# UNO_lowcost_V11.net
KiCad netlist of a schematic drawn in EAGLE
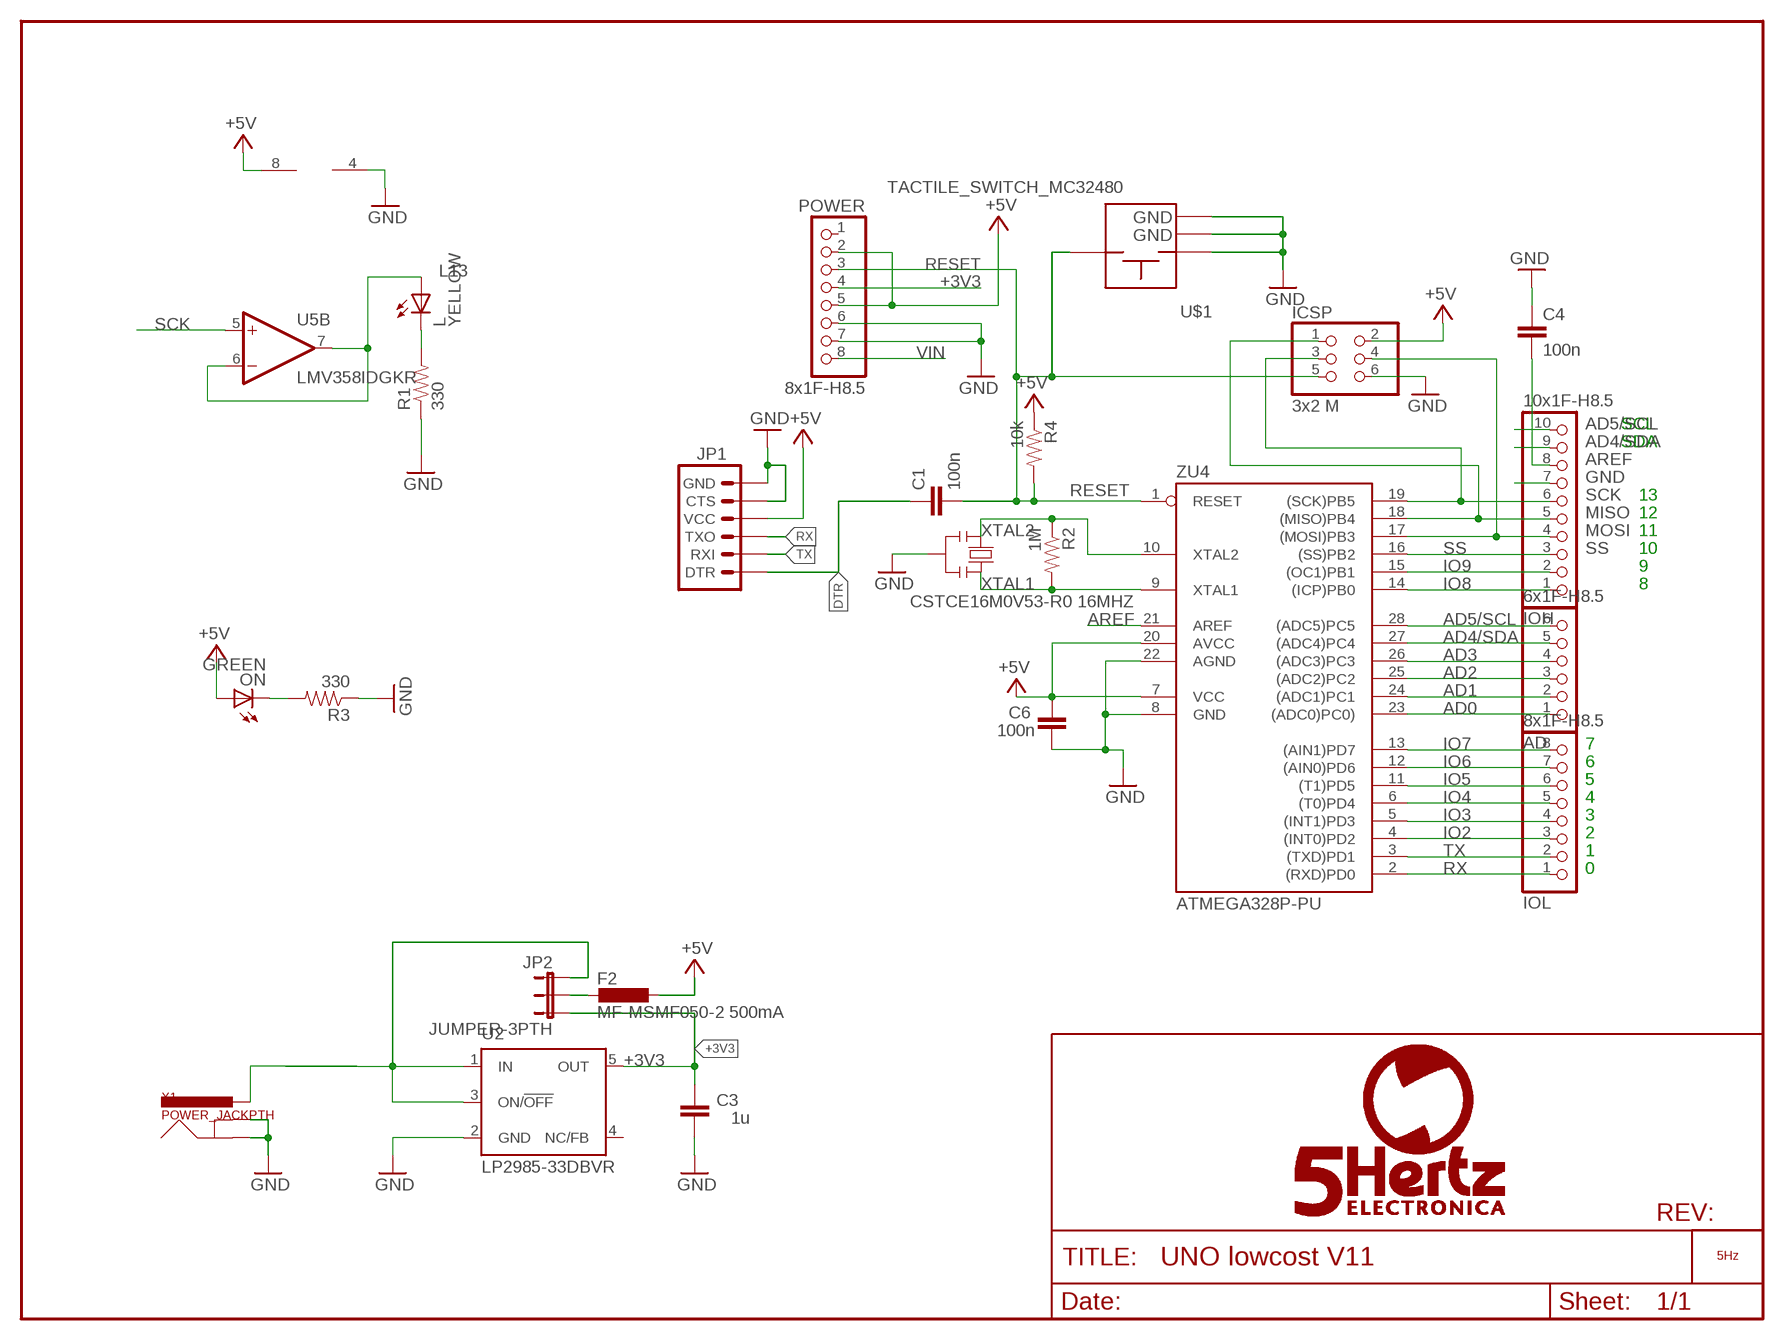
[diagram p0: schematic, sheet 1]

(export (version "E")
  (design (tool "Eeschema 10.0.6"))
  (components
    (comp (ref "AD")
      (value "6x1F-H8.5")
      (footprint "eagle-import:1X06")
      (libsource (lib "eagle-import") (part "PINHD-1X6"))
    )
    (comp (ref "C1")
      (value "100n")
      (footprint "eagle-import:C0603-ROUND")
      (libsource (lib "eagle-import") (part "C-EU0603-RND"))
    )
    (comp (ref "C3")
      (value "1u")
      (footprint "eagle-import:C0603-ROUND")
      (libsource (lib "eagle-import") (part "C-EU0603-RND"))
    )
    (comp (ref "C4")
      (value "100n")
      (footprint "eagle-import:C0603-ROUND")
      (libsource (lib "eagle-import") (part "C-EU0603-RND"))
    )
    (comp (ref "C6")
      (value "100n")
      (footprint "eagle-import:C0603-ROUND")
      (libsource (lib "eagle-import") (part "C-EU0603-RND"))
    )
    (comp (ref "F2")
      (value "MF-MSMF050-2 500mA")
      (footprint "eagle-import:L1812")
      (libsource (lib "eagle-import") (part "L-EUL1812"))
    )
    (comp (ref "ICSP")
      (value "3x2 M")
      (footprint "eagle-import:2X03")
      (libsource (lib "eagle-import") (part "PINHD-2X3"))
    )
    (comp (ref "IOH")
      (value "10x1F-H8.5")
      (footprint "eagle-import:1X10")
      (libsource (lib "eagle-import") (part "PINHD-1X10_ARD"))
    )
    (comp (ref "IOL")
      (value "8x1F-H8.5")
      (footprint "eagle-import:1X08")
      (libsource (lib "eagle-import") (part "PINHD-1X8"))
    )
    (comp (ref "JP1")
      (value "ARDUINO_SERIAL_PROGRAMPTH")
      (footprint "eagle-import:1X06")
      (libsource (lib "eagle-import") (part "ARDUINO_SERIAL_PROGRAMPTH"))
    )
    (comp (ref "JP2")
      (value "JUMPER-3PTH")
      (footprint "eagle-import:1X03")
      (libsource (lib "eagle-import") (part "JUMPER-3PTH"))
    )
    (comp (ref "L")
      (value "YELLOW")
      (footprint "eagle-import:CHIP-LED0603")
      (libsource (lib "eagle-import") (part "LEDCHIP-LED0603"))
    )
    (comp (ref "LOGO1")
      (value "LOGO_5HZ_H_20MM")
      (footprint "eagle-import:5HZ_LOGO_H_20MM")
      (libsource (lib "eagle-import") (part "LOGO_5HZ_H_20MM"))
    )
    (comp (ref "ON")
      (value "GREEN")
      (footprint "eagle-import:CHIP-LED0603")
      (libsource (lib "eagle-import") (part "LEDCHIP-LED0603"))
    )
    (comp (ref "POWER")
      (value "8x1F-H8.5")
      (footprint "eagle-import:1X08")
      (libsource (lib "eagle-import") (part "PINHD-1X8"))
    )
    (comp (ref "R1")
      (value "330")
      (footprint "eagle-import:0603-RES")
      (libsource (lib "eagle-import") (part "RESISTOR0603-RES"))
    )
    (comp (ref "R2")
      (value "1M")
      (footprint "eagle-import:0603-RES")
      (libsource (lib "eagle-import") (part "RESISTOR0603-RES"))
    )
    (comp (ref "R3")
      (value "330")
      (footprint "eagle-import:0603-RES")
      (libsource (lib "eagle-import") (part "RESISTOR0603-RES"))
    )
    (comp (ref "R4")
      (value "10k")
      (footprint "eagle-import:0603-RES")
      (libsource (lib "eagle-import") (part "RESISTOR0603-RES"))
    )
    (comp (ref "U$1")
      (value "TACTILE_SWITCH_MC32480")
      (footprint "eagle-import:MC32840")
      (libsource (lib "eagle-import") (part "TACTILE_SWITCH_MC32480"))
    )
    (comp (ref "U2")
      (value "LP2985-33DBVR")
      (footprint "eagle-import:SOT23-DBV")
      (libsource (lib "eagle-import") (part "LP2985-XXDBVR33"))
    )
    (comp (ref "U5")
      (value "LMV358IDGKR")
      (footprint "eagle-import:MSOP08")
      (libsource (lib "eagle-import") (part "LMV358?MMX"))
    )
    (comp (ref "X1")
      (value "POWER_JACKPTH")
      (footprint "eagle-import:POWER_JACK_PTH")
      (libsource (lib "eagle-import") (part "POWER_JACKPTH"))
    )
    (comp (ref "Y2")
      (value "CSTCE16M0V53-R0 16MHZ")
      (footprint "eagle-import:RESONATOR")
      (libsource (lib "eagle-import") (part "RESONATORMU"))
    )
    (comp (ref "ZU4")
      (value "ATMEGA328P-PU")
      (footprint "eagle-import:DIL28-3")
      (libsource (lib "eagle-import") (part "ATMEGA328P-PU"))
    )
  )
  (nets
    (net (code "1") (name "+3V3") (class "Default")
      (node (ref "C3") (pin "2") (pinfunction "2_2") (pintype "passive"))
      (node (ref "JP2") (pin "3") (pinfunction "3_3") (pintype "passive"))
      (node (ref "POWER") (pin "4") (pinfunction "4_4") (pintype "passive"))
      (node (ref "U2") (pin "5") (pinfunction "OUT_5") (pintype "passive"))
    )
    (net (code "2") (name "+5V") (class "Default")
      (node (ref "C6") (pin "2") (pinfunction "2_2") (pintype "passive"))
      (node (ref "F2") (pin "1") (pinfunction "1_1") (pintype "passive"))
      (node (ref "ICSP") (pin "2") (pinfunction "2_2") (pintype "passive"))
      (node (ref "JP1") (pin "4") (pinfunction "VCC_4") (pintype "passive"))
      (node (ref "ON") (pin "A") (pinfunction "A_A") (pintype "passive"))
      (node (ref "POWER") (pin "2") (pinfunction "2_2") (pintype "passive"))
      (node (ref "POWER") (pin "5") (pinfunction "5_5") (pintype "passive"))
      (node (ref "R4") (pin "1") (pinfunction "1_1") (pintype "passive"))
      (node (ref "U5") (pin "8") (pinfunction "V+_8") (pintype "power_in"))
      (node (ref "ZU4") (pin "20") (pinfunction "AVCC_20") (pintype "power_in"))
      (node (ref "ZU4") (pin "7") (pinfunction "VCC_7") (pintype "power_in"))
    )
    (net (code "3") (name "/AD0") (class "Default")
      (node (ref "AD") (pin "1") (pinfunction "1_1") (pintype "passive"))
      (node (ref "ZU4") (pin "23") (pinfunction "(ADC0)PC0)_23") (pintype "bidirectional"))
    )
    (net (code "4") (name "/AD1") (class "Default")
      (node (ref "AD") (pin "2") (pinfunction "2_2") (pintype "passive"))
      (node (ref "ZU4") (pin "24") (pinfunction "(ADC1)PC1_24") (pintype "bidirectional"))
    )
    (net (code "5") (name "/AD2") (class "Default")
      (node (ref "AD") (pin "3") (pinfunction "3_3") (pintype "passive"))
      (node (ref "ZU4") (pin "25") (pinfunction "(ADC2)PC2_25") (pintype "bidirectional"))
    )
    (net (code "6") (name "/AD3") (class "Default")
      (node (ref "AD") (pin "4") (pinfunction "4_4") (pintype "passive"))
      (node (ref "ZU4") (pin "26") (pinfunction "(ADC3)PC3_26") (pintype "bidirectional"))
    )
    (net (code "7") (name "/AD4{slash}SDA") (class "Default")
      (node (ref "AD") (pin "5") (pinfunction "5_5") (pintype "passive"))
      (node (ref "IOH") (pin "9") (pinfunction "9_9") (pintype "passive"))
      (node (ref "ZU4") (pin "27") (pinfunction "(ADC4)PC4_27") (pintype "bidirectional"))
    )
    (net (code "8") (name "/AD5{slash}SCL") (class "Default")
      (node (ref "AD") (pin "6") (pinfunction "6_6") (pintype "passive"))
      (node (ref "IOH") (pin "10") (pinfunction "10_10") (pintype "passive"))
      (node (ref "ZU4") (pin "28") (pinfunction "(ADC5)PC5_28") (pintype "bidirectional"))
    )
    (net (code "9") (name "/AREF") (class "Default")
      (node (ref "C4") (pin "2") (pinfunction "2_2") (pintype "passive"))
      (node (ref "IOH") (pin "8") (pinfunction "8_8") (pintype "passive"))
      (node (ref "ZU4") (pin "21") (pinfunction "AREF_21") (pintype "passive"))
    )
    (net (code "10") (name "/IO2") (class "Default")
      (node (ref "IOL") (pin "3") (pinfunction "3_3") (pintype "passive"))
      (node (ref "ZU4") (pin "4") (pinfunction "(INT0)PD2_4") (pintype "bidirectional"))
    )
    (net (code "11") (name "/IO3") (class "Default")
      (node (ref "IOL") (pin "4") (pinfunction "4_4") (pintype "passive"))
      (node (ref "ZU4") (pin "5") (pinfunction "(INT1)PD3_5") (pintype "bidirectional"))
    )
    (net (code "12") (name "/IO4") (class "Default")
      (node (ref "IOL") (pin "5") (pinfunction "5_5") (pintype "passive"))
      (node (ref "ZU4") (pin "6") (pinfunction "(T0)PD4_6") (pintype "bidirectional"))
    )
    (net (code "13") (name "/IO5") (class "Default")
      (node (ref "IOL") (pin "6") (pinfunction "6_6") (pintype "passive"))
      (node (ref "ZU4") (pin "11") (pinfunction "(T1)PD5_11") (pintype "bidirectional"))
    )
    (net (code "14") (name "/IO6") (class "Default")
      (node (ref "IOL") (pin "7") (pinfunction "7_7") (pintype "passive"))
      (node (ref "ZU4") (pin "12") (pinfunction "(AIN0)PD6_12") (pintype "bidirectional"))
    )
    (net (code "15") (name "/IO7") (class "Default")
      (node (ref "IOL") (pin "8") (pinfunction "8_8") (pintype "passive"))
      (node (ref "ZU4") (pin "13") (pinfunction "(AIN1)PD7_13") (pintype "bidirectional"))
    )
    (net (code "16") (name "/IO8") (class "Default")
      (node (ref "IOH") (pin "1") (pinfunction "1_1") (pintype "passive"))
      (node (ref "ZU4") (pin "14") (pinfunction "(ICP)PB0_14") (pintype "bidirectional"))
    )
    (net (code "17") (name "/IO9") (class "Default")
      (node (ref "IOH") (pin "2") (pinfunction "2_2") (pintype "passive"))
      (node (ref "ZU4") (pin "15") (pinfunction "(OC1)PB1_15") (pintype "bidirectional"))
    )
    (net (code "18") (name "/L13") (class "Default")
      (node (ref "L") (pin "A") (pinfunction "A_A") (pintype "passive"))
      (node (ref "U5") (pin "6") (pinfunction "-IN_6") (pintype "input"))
      (node (ref "U5") (pin "7") (pinfunction "OUT_7") (pintype "output"))
    )
    (net (code "19") (name "/MISO") (class "Default")
      (node (ref "ICSP") (pin "1") (pinfunction "1_1") (pintype "passive"))
      (node (ref "IOH") (pin "5") (pinfunction "5_5") (pintype "passive"))
      (node (ref "ZU4") (pin "18") (pinfunction "(MISO)PB4_18") (pintype "bidirectional"))
    )
    (net (code "20") (name "/MOSI") (class "Default")
      (node (ref "ICSP") (pin "4") (pinfunction "4_4") (pintype "passive"))
      (node (ref "IOH") (pin "4") (pinfunction "4_4") (pintype "passive"))
      (node (ref "ZU4") (pin "17") (pinfunction "(MOSI)PB3_17") (pintype "bidirectional"))
    )
    (net (code "21") (name "/RESET") (class "Default")
      (node (ref "C1") (pin "2") (pinfunction "2_2") (pintype "passive"))
      (node (ref "ICSP") (pin "5") (pinfunction "5_5") (pintype "passive"))
      (node (ref "POWER") (pin "3") (pinfunction "3_3") (pintype "passive"))
      (node (ref "R4") (pin "2") (pinfunction "2_2") (pintype "passive"))
      (node (ref "U$1") (pin "B") (pinfunction "B_B") (pintype "passive"))
      (node (ref "ZU4") (pin "1") (pinfunction "RESET_1") (pintype "input"))
    )
    (net (code "22") (name "/SCK") (class "Default")
      (node (ref "ICSP") (pin "3") (pinfunction "3_3") (pintype "passive"))
      (node (ref "IOH") (pin "6") (pinfunction "6_6") (pintype "passive"))
      (node (ref "U5") (pin "5") (pinfunction "+IN_5") (pintype "input"))
      (node (ref "ZU4") (pin "19") (pinfunction "(SCK)PB5_19") (pintype "bidirectional"))
    )
    (net (code "23") (name "/SS") (class "Default")
      (node (ref "IOH") (pin "3") (pinfunction "3_3") (pintype "passive"))
      (node (ref "ZU4") (pin "16") (pinfunction "(SS)PB2_16") (pintype "bidirectional"))
    )
    (net (code "24") (name "/VIN") (class "Default")
      (node (ref "JP2") (pin "1") (pinfunction "1_1") (pintype "passive"))
      (node (ref "POWER") (pin "8") (pinfunction "8_8") (pintype "passive"))
      (node (ref "U2") (pin "1") (pinfunction "IN_1") (pintype "input"))
      (node (ref "U2") (pin "3") (pinfunction "ON/~{OFF}_3") (pintype "input"))
      (node (ref "X1") (pin "PWR") (pinfunction "PWR_PWR") (pintype "bidirectional"))
    )
    (net (code "25") (name "/XTAL1") (class "Default")
      (node (ref "R2") (pin "2") (pinfunction "2_2") (pintype "passive"))
      (node (ref "Y2") (pin "3") (pinfunction "3_3") (pintype "passive"))
      (node (ref "ZU4") (pin "9") (pinfunction "XTAL1_9") (pintype "bidirectional"))
    )
    (net (code "26") (name "/XTAL2") (class "Default")
      (node (ref "R2") (pin "1") (pinfunction "1_1") (pintype "passive"))
      (node (ref "Y2") (pin "1") (pinfunction "1_1") (pintype "passive"))
      (node (ref "ZU4") (pin "10") (pinfunction "XTAL2_10") (pintype "bidirectional"))
    )
    (net (code "27") (name "DTR") (class "Default")
      (node (ref "C1") (pin "1") (pinfunction "1_1") (pintype "passive"))
      (node (ref "JP1") (pin "1") (pinfunction "DTR_1") (pintype "passive"))
    )
    (net (code "28") (name "GND") (class "Default")
      (node (ref "C3") (pin "1") (pinfunction "1_1") (pintype "passive"))
      (node (ref "C4") (pin "1") (pinfunction "1_1") (pintype "passive"))
      (node (ref "C6") (pin "1") (pinfunction "1_1") (pintype "passive"))
      (node (ref "ICSP") (pin "6") (pinfunction "6_6") (pintype "passive"))
      (node (ref "IOH") (pin "7") (pinfunction "7_7") (pintype "passive"))
      (node (ref "JP1") (pin "5") (pinfunction "CTS_5") (pintype "passive"))
      (node (ref "JP1") (pin "6") (pinfunction "GND_6") (pintype "passive"))
      (node (ref "POWER") (pin "6") (pinfunction "6_6") (pintype "passive"))
      (node (ref "POWER") (pin "7") (pinfunction "7_7") (pintype "passive"))
      (node (ref "R1") (pin "1") (pinfunction "1_1") (pintype "passive"))
      (node (ref "R3") (pin "1") (pinfunction "1_1") (pintype "passive"))
      (node (ref "U$1") (pin "A@1") (pinfunction "A_A@1") (pintype "passive"))
      (node (ref "U$1") (pin "GND@1") (pinfunction "GND_GND@1") (pintype "bidirectional"))
      (node (ref "U$1") (pin "GND@2") (pinfunction "GND_GND@2") (pintype "bidirectional"))
      (node (ref "U2") (pin "2") (pinfunction "GND_2") (pintype "power_in"))
      (node (ref "U5") (pin "4") (pinfunction "V-_4") (pintype "power_in"))
      (node (ref "X1") (pin "GND") (pinfunction "GND_GND") (pintype "bidirectional"))
      (node (ref "X1") (pin "GNDBREAK") (pinfunction "GNDBREAK_GNDBREAK") (pintype "bidirectional"))
      (node (ref "Y2") (pin "2") (pinfunction "2_2") (pintype "passive"))
      (node (ref "ZU4") (pin "22") (pinfunction "AGND_22") (pintype "power_in"))
      (node (ref "ZU4") (pin "8") (pinfunction "GND_8") (pintype "power_in"))
    )
    (net (code "29") (name "Net-(F2-Pad2)") (class "Default")
      (node (ref "F2") (pin "2") (pinfunction "2_2") (pintype "passive"))
      (node (ref "JP2") (pin "2") (pinfunction "2_2") (pintype "passive"))
    )
    (net (code "30") (name "Net-(L-PadC)") (class "Default")
      (node (ref "L") (pin "C") (pinfunction "C_C") (pintype "passive"))
      (node (ref "R1") (pin "2") (pinfunction "2_2") (pintype "passive"))
    )
    (net (code "31") (name "Net-(ON-PadC)") (class "Default")
      (node (ref "ON") (pin "C") (pinfunction "C_C") (pintype "passive"))
      (node (ref "R3") (pin "2") (pinfunction "2_2") (pintype "passive"))
    )
    (net (code "32") (name "RX") (class "Default")
      (node (ref "IOL") (pin "1") (pinfunction "1_1") (pintype "passive"))
      (node (ref "JP1") (pin "3") (pinfunction "TXO_3") (pintype "passive"))
      (node (ref "ZU4") (pin "2") (pinfunction "(RXD)PD0_2") (pintype "bidirectional"))
    )
    (net (code "33") (name "TX") (class "Default")
      (node (ref "IOL") (pin "2") (pinfunction "2_2") (pintype "passive"))
      (node (ref "JP1") (pin "2") (pinfunction "RXI_2") (pintype "passive"))
      (node (ref "ZU4") (pin "3") (pinfunction "(TXD)PD1_3") (pintype "bidirectional"))
    )
    (net (code "34") (name "unconnected-(POWER-Pad1)") (class "Default")
      (node (ref "POWER") (pin "1") (pinfunction "1_1") (pintype "passive"))
    )
    (net (code "35") (name "unconnected-(U2-NC{slash}FB-Pad4)") (class "Default")
      (node (ref "U2") (pin "4") (pinfunction "NC/FB_4") (pintype "passive"))
    )
  )
)
